# RTC.net
KiCad netlist of a schematic drawn in Altium Designer
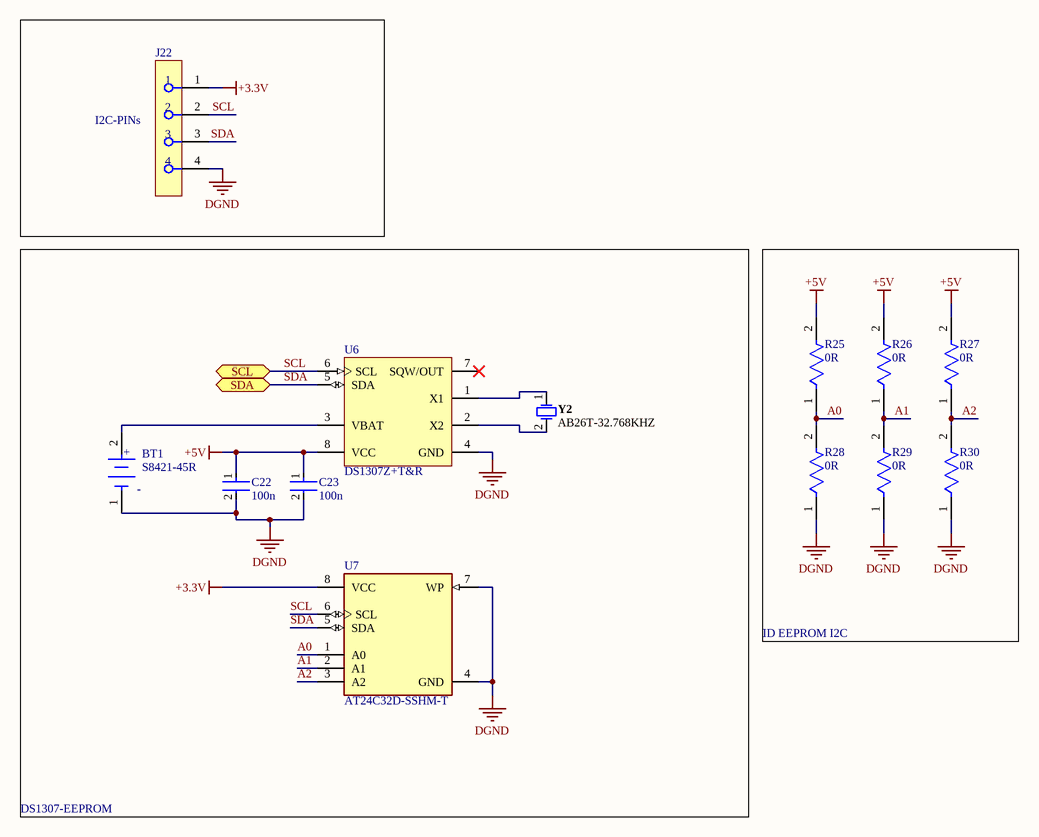
[diagram p0: RTC.SchDoc]

(export (version "E")
  (design (tool "Eeschema 10.0.6"))
  (components
    (comp (ref "BT1")
      (value "S8421-45R")
      (footprint "FP-S8421-45R-MFG")
      (description "BATTERY HOLDER COIN 20MM SMD")
      (libsource (lib "Altium Content Vault") (part "60d3b5b901a8747834971d0eb8cf3fd"))
    )
    (comp (ref "C22")
      (value "100n")
      (footprint "FP-C0805C-DN-MFG")
      (description "CAP 100nf 20% 0805")
      (fields
        (field (name "OCTOPART") "https://octopart.com/c0805c101j1gac7210-kemet-9145156")
        (field (name "MANUFACTURER") "KEMET")
      )
      (libsource (lib "Altium Content Vault") (part "b4654b650e69147ec39a6b967a45e02"))
    )
    (comp (ref "C23")
      (value "100n")
      (footprint "FP-C0805C-DN-MFG")
      (description "CAP 100nf 20% 0805")
      (fields
        (field (name "OCTOPART") "https://octopart.com/c0805c101j1gac7210-kemet-9145156")
        (field (name "MANUFACTURER") "KEMET")
      )
      (libsource (lib "Altium Content Vault") (part "b4654b650e69147ec39a6b967a45e02"))
    )
    (comp (ref "J22")
      (value "I2C-PINs")
      (footprint "FP-ESW-104-23-G-S-MFG")
      (description "HEADER PINS 4 POS / I2C Pins")
      (libsource (lib "Altium Content Vault") (part "ESW-104-23-G-S"))
    )
    (comp (ref "R25")
      (value "0R")
      (footprint "FP-TLRZ1E-MFG")
      (description "RES 0R 5% 0805")
      (libsource (lib "Altium Content Vault") (part "1029c3af85768c4190bb7ad29bc67b5"))
    )
    (comp (ref "R26")
      (value "0R")
      (footprint "FP-TLRZ1E-MFG")
      (description "RES 0R 5% 0805")
      (libsource (lib "Altium Content Vault") (part "1029c3af85768c4190bb7ad29bc67b5"))
    )
    (comp (ref "R27")
      (value "0R")
      (footprint "FP-TLRZ1E-MFG")
      (description "RES 0R 5% 0805")
      (libsource (lib "Altium Content Vault") (part "1029c3af85768c4190bb7ad29bc67b5"))
    )
    (comp (ref "R28")
      (value "0R")
      (footprint "FP-TLRZ1E-MFG")
      (description "RES 0R 5% 0805")
      (libsource (lib "Altium Content Vault") (part "1029c3af85768c4190bb7ad29bc67b5"))
    )
    (comp (ref "R29")
      (value "0R")
      (footprint "FP-TLRZ1E-MFG")
      (description "RES 0R 5% 0805")
      (libsource (lib "Altium Content Vault") (part "1029c3af85768c4190bb7ad29bc67b5"))
    )
    (comp (ref "R30")
      (value "0R")
      (footprint "FP-TLRZ1E-MFG")
      (description "RES 0R 5% 0805")
      (libsource (lib "Altium Content Vault") (part "1029c3af85768c4190bb7ad29bc67b5"))
    )
    (comp (ref "U6")
      (value "DS1307Z+T&R")
      (footprint "S8+2_L")
      (description "CI DS1307")
      (libsource (lib "Altium Content Vault") (part "PR_RTC_DS1307-IL8"))
    )
    (comp (ref "U7")
      (value "AT24C32D-SSHM-T")
      (footprint "FP-C04-057-SN-IPC_C")
      (description "CI EEPROM 32K I2C 1MHZ 8SOIC")
      (libsource (lib "Altium Content Vault") (part "e0cfc16659b612be14ebcb69d530ce7"))
    )
    (comp (ref "Y2")
      (value "AB26T-32.768KHZ")
      (footprint "ABRA-AB26T")
      (description "CRYSTAL 32.768KHz RTC")
      (fields (field (name "MANUFACTURER") "ABRACON") (field (name "TOLERANCE") "20PPM"))
      (libsource (lib "Altium Content Vault") (part "XTAL-1-2-2"))
    )
  )
  (nets
    (net (code "1") (name "+3.3V") (class "Default")
      (node (ref "J22") (pin "1") (pinfunction "1_1") (pintype "passive"))
      (node (ref "U7") (pin "8") (pinfunction "VCC_8") (pintype "power_in"))
    )
    (net (code "2") (name "+5V") (class "Default")
      (node (ref "C22") (pin "1") (pinfunction "1_1") (pintype "passive"))
      (node (ref "C23") (pin "1") (pinfunction "1_1") (pintype "passive"))
      (node (ref "R25") (pin "2") (pinfunction "2_2") (pintype "passive"))
      (node (ref "R26") (pin "2") (pinfunction "2_2") (pintype "passive"))
      (node (ref "R27") (pin "2") (pinfunction "2_2") (pintype "passive"))
      (node (ref "U6") (pin "8") (pinfunction "VCC_8") (pintype "power_in"))
    )
    (net (code "3") (name "/A0") (class "Default")
      (node (ref "R25") (pin "1") (pinfunction "1_1") (pintype "passive"))
      (node (ref "R28") (pin "2") (pinfunction "2_2") (pintype "passive"))
      (node (ref "U7") (pin "1") (pinfunction "A0_1") (pintype "passive"))
    )
    (net (code "4") (name "/A1") (class "Default")
      (node (ref "R26") (pin "1") (pinfunction "1_1") (pintype "passive"))
      (node (ref "R29") (pin "2") (pinfunction "2_2") (pintype "passive"))
      (node (ref "U7") (pin "2") (pinfunction "A1_2") (pintype "passive"))
    )
    (net (code "5") (name "/A2") (class "Default")
      (node (ref "R27") (pin "1") (pinfunction "1_1") (pintype "passive"))
      (node (ref "R30") (pin "2") (pinfunction "2_2") (pintype "passive"))
      (node (ref "U7") (pin "3") (pinfunction "A2_3") (pintype "passive"))
    )
    (net (code "6") (name "/SCL") (class "Default")
      (node (ref "J22") (pin "2") (pinfunction "2_2") (pintype "passive"))
      (node (ref "U6") (pin "6") (pinfunction "SCL_6") (pintype "input"))
      (node (ref "U7") (pin "6") (pinfunction "SCL_6") (pintype "bidirectional"))
    )
    (net (code "7") (name "/SDA") (class "Default")
      (node (ref "J22") (pin "3") (pinfunction "3_3") (pintype "passive"))
      (node (ref "U6") (pin "5") (pinfunction "SDA_5") (pintype "bidirectional"))
      (node (ref "U7") (pin "5") (pinfunction "SDA_5") (pintype "bidirectional"))
    )
    (net (code "8") (name "DGND") (class "Default")
      (node (ref "BT1") (pin "1") (pinfunction "C_1") (pintype "passive"))
      (node (ref "C22") (pin "2") (pinfunction "2_2") (pintype "passive"))
      (node (ref "C23") (pin "2") (pinfunction "2_2") (pintype "passive"))
      (node (ref "J22") (pin "4") (pinfunction "4_4") (pintype "passive"))
      (node (ref "R28") (pin "1") (pinfunction "1_1") (pintype "passive"))
      (node (ref "R29") (pin "1") (pinfunction "1_1") (pintype "passive"))
      (node (ref "R30") (pin "1") (pinfunction "1_1") (pintype "passive"))
      (node (ref "U6") (pin "4") (pinfunction "GND_4") (pintype "power_in"))
      (node (ref "U7") (pin "4") (pinfunction "GND_4") (pintype "power_in"))
      (node (ref "U7") (pin "7") (pinfunction "WP_7") (pintype "input"))
    )
    (net (code "9") (name "Net-(BT1-A)") (class "Default")
      (node (ref "BT1") (pin "2") (pinfunction "A_2") (pintype "passive"))
      (node (ref "U6") (pin "3") (pinfunction "VBAT_3") (pintype "power_in"))
    )
    (net (code "10") (name "Net-(U6-X1)") (class "Default")
      (node (ref "U6") (pin "1") (pinfunction "X1_1") (pintype "passive"))
      (node (ref "Y2") (pin "1") (pinfunction "1_1") (pintype "passive"))
    )
    (net (code "11") (name "Net-(U6-X2)") (class "Default")
      (node (ref "U6") (pin "2") (pinfunction "X2_2") (pintype "passive"))
      (node (ref "Y2") (pin "2") (pinfunction "2_2") (pintype "passive"))
    )
    (net (code "12") (name "unconnected-(U6-SQW{slash}OUT-Pad7)") (class "Default")
      (node (ref "U6") (pin "7") (pinfunction "SQW/OUT_7") (pintype "open_collector+no_connect"))
    )
  )
)
